# 1_power.net
KiCad netlist of a schematic drawn in Altium Designer
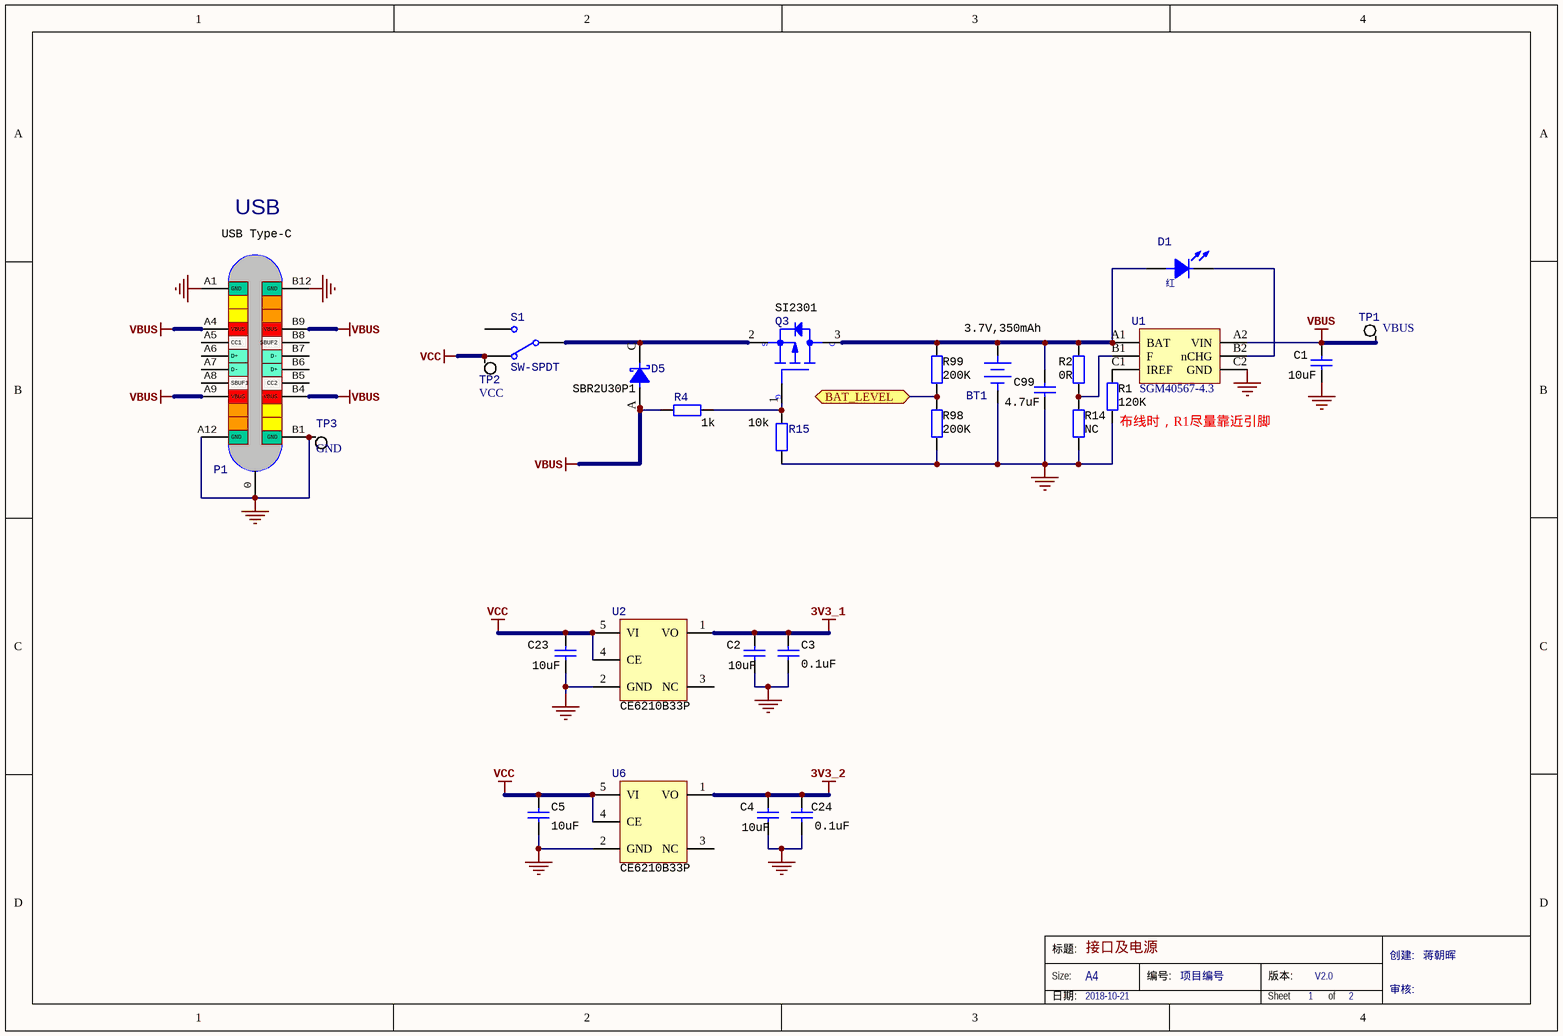
[diagram p0: 1.power.SchDoc]

(export (version "E")
  (design (tool "Eeschema 10.0.6"))
  (components
    (comp (ref "BT1")
      (value "3.7V,350mAh")
      (footprint "2P/1.0MM立式贴片座子")
      (description "4.2V Li-lon")
      (fields (field (name "MANUFACTURER") "?"))
      (libsource (lib "03.常用器件") (part "Battery"))
    )
    (comp (ref "C1")
      (value "10uF")
      (footprint "C0603")
      (description "CAP, CERM, 0.01uF, 100V, +/-5%, X7R, 0603")
      (fields (field (name "PARTNUMBER") "06031C103JAT2A") (field (name "MANUFACTURER") "AVX"))
      (libsource (lib "03.常用器件") (part "CAP1_npol"))
    )
    (comp (ref "C2")
      (value "10uF")
      (footprint "0603")
      (description "CAP, CERM, 0.01uF, 100V, +/-5%, X7R, 0603")
      (fields (field (name "PARTNUMBER") "06031C103JAT2A") (field (name "MANUFACTURER") "AVX"))
      (libsource (lib "03.常用器件") (part "CAP1_npol"))
    )
    (comp (ref "C3")
      (value "0.1uF")
      (footprint "0402")
      (description "CAP, CERM, 0.01uF, 100V, +/-5%, X7R, 0603")
      (fields (field (name "PARTNUMBER") "06031C103JAT2A") (field (name "MANUFACTURER") "AVX"))
      (libsource (lib "03.常用器件") (part "CAP1_npol"))
    )
    (comp (ref "C4")
      (value "10uF")
      (footprint "0603")
      (description "CAP, CERM, 0.01uF, 100V, +/-5%, X7R, 0603")
      (fields (field (name "PARTNUMBER") "06031C103JAT2A") (field (name "MANUFACTURER") "AVX"))
      (libsource (lib "03.常用器件") (part "CAP1_npol"))
    )
    (comp (ref "C5")
      (value "10uF")
      (footprint "0603")
      (description "CAP, CERM, 0.01uF, 100V, +/-5%, X7R, 0603")
      (fields (field (name "PARTNUMBER") "06031C103JAT2A") (field (name "MANUFACTURER") "AVX"))
      (libsource (lib "03.常用器件") (part "CAP1_npol"))
    )
    (comp (ref "C23")
      (value "10uF")
      (footprint "0603")
      (description "CAP, CERM, 0.01uF, 100V, +/-5%, X7R, 0603")
      (fields (field (name "PARTNUMBER") "06031C103JAT2A") (field (name "MANUFACTURER") "AVX"))
      (libsource (lib "03.常用器件") (part "CAP1_npol"))
    )
    (comp (ref "C24")
      (value "0.1uF")
      (footprint "0402")
      (description "CAP, CERM, 0.01uF, 100V, +/-5%, X7R, 0603")
      (fields (field (name "PARTNUMBER") "06031C103JAT2A") (field (name "MANUFACTURER") "AVX"))
      (libsource (lib "03.常用器件") (part "CAP1_npol"))
    )
    (comp (ref "C99")
      (value "4.7uF")
      (footprint "C0603")
      (description "CAP, CERM, 0.01uF, 100V, +/-5%, X7R, 0603")
      (fields (field (name "PARTNUMBER") "06031C103JAT2A") (field (name "MANUFACTURER") "AVX"))
      (libsource (lib "03.常用器件") (part "CAP1_npol"))
    )
    (comp (ref "D1")
      (value "红")
      (footprint "0603LED")
      (fields (field (name "MANUFACTURER") "?"))
      (libsource (lib "03.常用器件") (part "LED1"))
    )
    (comp (ref "D5")
      (value "SBR2U30P1")
      (footprint "POWERDI123")
      (fields (field (name "PARTNUMBER") "?") (field (name "PUBLISHER") "Altium Limited"))
      (libsource (lib "03.常用器件") (part "Diode_Schottky"))
    )
    (comp (ref "P1")
      (value "USB Type-C")
      (footprint "TYPC-16PIN")
      (libsource (lib "USB Type-C") (part "USB Type-C"))
    )
    (comp (ref "Q3")
      (value "SI2301")
      (footprint "SOT23-3")
      (fields (field (name "MANUFACTURER") "?"))
      (libsource (lib "03.常用器件") (part "PMOS"))
    )
    (comp (ref "R1")
      (value "120K")
      (footprint "R0402")
      (description "RES, 1.0k ohm, 5%, 0.1W, 0603")
      (fields
        (field (name "PARTNUMBER") "RC0603JR-071KL")
        (field (name "MANUFACTURER") "Yageo America")
        (field (name "PUBLISHER") "Texas Instruments")
      )
      (libsource (lib "03.常用器件") (part "RES1"))
    )
    (comp (ref "R2")
      (value "0R")
      (footprint "R0402")
      (description "RES, 1.0k ohm, 5%, 0.1W, 0603")
      (fields
        (field (name "PARTNUMBER") "RC0603JR-071KL")
        (field (name "MANUFACTURER") "Yageo America")
        (field (name "PUBLISHER") "Texas Instruments")
      )
      (libsource (lib "") (part "RES1_1"))
    )
    (comp (ref "R4")
      (value "1k")
      (footprint "R0402")
      (description "Resistor")
      (fields (field (name "PUBLISHER") "Altium Limited"))
      (libsource (lib "Miscellaneous Devices") (part "Res2"))
    )
    (comp (ref "R14")
      (value "NC")
      (footprint "R0402")
      (description "RES, 1.0k ohm, 5%, 0.1W, 0603")
      (fields
        (field (name "PARTNUMBER") "RC0603JR-071KL")
        (field (name "MANUFACTURER") "Yageo America")
        (field (name "PUBLISHER") "Texas Instruments")
      )
      (libsource (lib "") (part "RES1_1"))
    )
    (comp (ref "R15")
      (value "10k")
      (footprint "R0402")
      (description "Resistor")
      (fields (field (name "PUBLISHER") "Altium Limited"))
      (libsource (lib "") (part "Res2_1"))
    )
    (comp (ref "R98")
      (value "200K")
      (footprint "R0402")
      (description "RES, 1.0k ohm, 5%, 0.1W, 0603")
      (fields
        (field (name "PARTNUMBER") "RC0603JR-071KL")
        (field (name "MANUFACTURER") "Yageo America")
        (field (name "PUBLISHER") "Texas Instruments")
      )
      (libsource (lib "03.常用器件") (part "RES1"))
    )
    (comp (ref "R99")
      (value "200K")
      (footprint "R0402")
      (description "RES, 1.0k ohm, 5%, 0.1W, 0603")
      (fields
        (field (name "PARTNUMBER") "RC0603JR-071KL")
        (field (name "MANUFACTURER") "Yageo America")
        (field (name "PUBLISHER") "Texas Instruments")
      )
      (libsource (lib "03.常用器件") (part "RES1"))
    )
    (comp (ref "S1")
      (value "SW-SPDT")
      (footprint "SW2")
      (description "SPDT Subminiature Toggle Switch, Right Angle Mounting, Vertical Actuation")
      (fields (field (name "PUBLISHER") "Altium Limited"))
      (libsource (lib "Miscellaneous Devices") (part "SW-SPDT"))
    )
    (comp (ref "TP1")
      (value "VBUS")
      (footprint "测试点")
      (description "Test Point")
      (libsource (lib "my_Schlib") (part "TP"))
    )
    (comp (ref "TP2")
      (value "VCC")
      (footprint "测试点")
      (description "Test Point")
      (libsource (lib "my_Schlib") (part "TP"))
    )
    (comp (ref "TP3")
      (value "GND")
      (footprint "测试点")
      (description "Test Point")
      (libsource (lib "my_Schlib") (part "TP"))
    )
    (comp (ref "U1")
      (value "SGM40567-4.3")
      (footprint "SGM40567")
      (description "充电IC")
      (libsource (lib "SGM40567") (part "SGM40567"))
    )
    (comp (ref "U2")
      (value "CE6210B33P")
      (footprint "SOT89-5")
      (libsource (lib "altium-import") (part "root_0_AP2112K_"))
    )
    (comp (ref "U6")
      (value "CE6210B33P")
      (footprint "SOT89-5")
      (libsource (lib "altium-import") (part "root_0_AP2112K_"))
    )
  )
  (nets
    (net (code "1") (name "/BAT_LEVEL") (class "Default")
      (node (ref "R98") (pin "2") (pinfunction "2_2") (pintype "passive"))
      (node (ref "R99") (pin "1") (pinfunction "1_1") (pintype "passive"))
    )
    (net (code "2") (name "3V3_1") (class "Default")
      (node (ref "C2") (pin "1") (pinfunction "1_1") (pintype "passive"))
      (node (ref "C3") (pin "2") (pinfunction "2_2") (pintype "passive"))
      (node (ref "U2") (pin "1") (pinfunction "VO_1") (pintype "passive"))
    )
    (net (code "3") (name "3V3_2") (class "Default")
      (node (ref "C24") (pin "2") (pinfunction "2_2") (pintype "passive"))
      (node (ref "C4") (pin "1") (pinfunction "1_1") (pintype "passive"))
      (node (ref "U6") (pin "1") (pinfunction "VO_1") (pintype "passive"))
    )
    (net (code "4") (name "<NO NET>") (class "Default")
      (node (ref "BT1") (pin "2") (pinfunction "-_2") (pintype "passive"))
      (node (ref "C1") (pin "2") (pinfunction "2_2") (pintype "passive"))
      (node (ref "C2") (pin "2") (pinfunction "2_2") (pintype "passive"))
      (node (ref "C23") (pin "2") (pinfunction "2_2") (pintype "passive"))
      (node (ref "C24") (pin "1") (pinfunction "1_1") (pintype "passive"))
      (node (ref "C3") (pin "1") (pinfunction "1_1") (pintype "passive"))
      (node (ref "C4") (pin "2") (pinfunction "2_2") (pintype "passive"))
      (node (ref "C5") (pin "2") (pinfunction "2_2") (pintype "passive"))
      (node (ref "C99") (pin "2") (pinfunction "2_2") (pintype "passive"))
      (node (ref "P1") (pin "0") (pinfunction "Shield_0") (pintype "passive"))
      (node (ref "P1") (pin "A1") (pinfunction "GND_A1") (pintype "passive"))
      (node (ref "P1") (pin "A12") (pinfunction "GND_A12") (pintype "passive"))
      (node (ref "P1") (pin "B1") (pinfunction "GND_B1") (pintype "passive"))
      (node (ref "P1") (pin "B12") (pinfunction "GND_B12") (pintype "passive"))
      (node (ref "R1") (pin "1") (pinfunction "1_1") (pintype "passive"))
      (node (ref "R14") (pin "2") (pinfunction "2_2") (pintype "passive"))
      (node (ref "R15") (pin "1") (pinfunction "1_1") (pintype "passive"))
      (node (ref "R98") (pin "1") (pinfunction "1_1") (pintype "passive"))
      (node (ref "TP3") (pin "1") (pinfunction "1_1") (pintype "passive"))
      (node (ref "U1") (pin "C2") (pinfunction "GND_C2") (pintype "passive"))
      (node (ref "U2") (pin "2") (pinfunction "GND_2") (pintype "passive"))
      (node (ref "U6") (pin "2") (pinfunction "GND_2") (pintype "passive"))
    )
    (net (code "5") (name "Net-(BT1-+)") (class "Default")
      (node (ref "BT1") (pin "1") (pinfunction "+_1") (pintype "passive"))
      (node (ref "C99") (pin "1") (pinfunction "1_1") (pintype "passive"))
      (node (ref "D1") (pin "A") (pinfunction "ANODE_A") (pintype "passive"))
      (node (ref "Q3") (pin "3") (pinfunction "DRAIN_3") (pintype "passive"))
      (node (ref "R2") (pin "1") (pinfunction "1_1") (pintype "passive"))
      (node (ref "R99") (pin "2") (pinfunction "2_2") (pintype "passive"))
      (node (ref "U1") (pin "A1") (pinfunction "BAT_A1") (pintype "passive"))
    )
    (net (code "6") (name "Net-(D1-CATHODE)") (class "Default")
      (node (ref "D1") (pin "C") (pinfunction "CATHODE_C") (pintype "passive"))
      (node (ref "U1") (pin "B2") (pinfunction "nCHG_B2") (pintype "passive"))
    )
    (net (code "7") (name "Net-(D5-CATHODE)") (class "Default")
      (node (ref "D5") (pin "C") (pinfunction "CATHODE_C") (pintype "passive"))
      (node (ref "Q3") (pin "2") (pinfunction "SOURCE_2") (pintype "passive"))
      (node (ref "S1") (pin "2") (pinfunction "2_2") (pintype "passive"))
    )
    (net (code "8") (name "Net-(Q3-GATE)") (class "Default")
      (node (ref "Q3") (pin "1") (pinfunction "GATE_1") (pintype "passive"))
      (node (ref "R15") (pin "2") (pinfunction "2_2") (pintype "passive"))
      (node (ref "R4") (pin "1") (pinfunction "1_1") (pintype "passive"))
    )
    (net (code "9") (name "Net-(U1-F)") (class "Default")
      (node (ref "R14") (pin "1") (pinfunction "1_1") (pintype "passive"))
      (node (ref "R2") (pin "2") (pinfunction "2_2") (pintype "passive"))
      (node (ref "U1") (pin "B1") (pinfunction "F_B1") (pintype "passive"))
    )
    (net (code "10") (name "Net-(U1-IREF)") (class "Default")
      (node (ref "R1") (pin "2") (pinfunction "2_2") (pintype "passive"))
      (node (ref "U1") (pin "C1") (pinfunction "IREF_C1") (pintype "passive"))
    )
    (net (code "11") (name "VBUS") (class "Default")
      (node (ref "C1") (pin "1") (pinfunction "1_1") (pintype "passive"))
      (node (ref "D5") (pin "A") (pinfunction "ANODE_A") (pintype "passive"))
      (node (ref "P1") (pin "A4") (pinfunction "VBUS_A4") (pintype "passive"))
      (node (ref "P1") (pin "A9") (pinfunction "VBUS_A9") (pintype "passive"))
      (node (ref "P1") (pin "B4") (pinfunction "VBUS_B4") (pintype "passive"))
      (node (ref "P1") (pin "B9") (pinfunction "VBUS_B9") (pintype "passive"))
      (node (ref "R4") (pin "2") (pinfunction "2_2") (pintype "passive"))
      (node (ref "TP1") (pin "1") (pinfunction "1_1") (pintype "passive"))
      (node (ref "U1") (pin "A2") (pinfunction "VIN_A2") (pintype "passive"))
    )
    (net (code "12") (name "VCC") (class "Default")
      (node (ref "C23") (pin "1") (pinfunction "1_1") (pintype "passive"))
      (node (ref "C5") (pin "1") (pinfunction "1_1") (pintype "passive"))
      (node (ref "S1") (pin "3") (pinfunction "3_3") (pintype "passive"))
      (node (ref "TP2") (pin "1") (pinfunction "1_1") (pintype "passive"))
      (node (ref "U2") (pin "4") (pinfunction "CE_4") (pintype "passive"))
      (node (ref "U2") (pin "5") (pinfunction "VI_5") (pintype "passive"))
      (node (ref "U6") (pin "4") (pinfunction "CE_4") (pintype "passive"))
      (node (ref "U6") (pin "5") (pinfunction "VI_5") (pintype "passive"))
    )
    (net (code "13") (name "unconnected-(P1-CC1-PadA5)") (class "Default")
      (node (ref "P1") (pin "A5") (pinfunction "CC1_A5") (pintype "passive"))
    )
    (net (code "14") (name "unconnected-(P1-CC2-PadB5)") (class "Default")
      (node (ref "P1") (pin "B5") (pinfunction "CC2_B5") (pintype "passive"))
    )
    (net (code "15") (name "unconnected-(P1-D+-PadA6)") (class "Default")
      (node (ref "P1") (pin "A6") (pinfunction "D+_A6") (pintype "passive"))
    )
    (net (code "16") (name "unconnected-(P1-D+-PadB6)") (class "Default")
      (node (ref "P1") (pin "B6") (pinfunction "D+_B6") (pintype "passive"))
    )
    (net (code "17") (name "unconnected-(P1-D--PadA7)") (class "Default")
      (node (ref "P1") (pin "A7") (pinfunction "D-_A7") (pintype "passive"))
    )
    (net (code "18") (name "unconnected-(P1-D--PadB7)") (class "Default")
      (node (ref "P1") (pin "B7") (pinfunction "D-_B7") (pintype "passive"))
    )
    (net (code "19") (name "unconnected-(P1-SBUF1-PadA8)") (class "Default")
      (node (ref "P1") (pin "A8") (pinfunction "SBUF1_A8") (pintype "passive"))
    )
    (net (code "20") (name "unconnected-(P1-SBUF2-PadB8)") (class "Default")
      (node (ref "P1") (pin "B8") (pinfunction "SBUF2_B8") (pintype "passive"))
    )
    (net (code "21") (name "unconnected-(S1-Pad1)") (class "Default")
      (node (ref "S1") (pin "1") (pinfunction "1_1") (pintype "passive"))
    )
    (net (code "22") (name "unconnected-(U2-NC-Pad3)") (class "Default")
      (node (ref "U2") (pin "3") (pinfunction "NC_3") (pintype "passive"))
    )
    (net (code "23") (name "unconnected-(U6-NC-Pad3)") (class "Default")
      (node (ref "U6") (pin "3") (pinfunction "NC_3") (pintype "passive"))
    )
  )
)
